# 4_Ethernet_PHY.net
KiCad netlist of a schematic drawn in Altium Designer
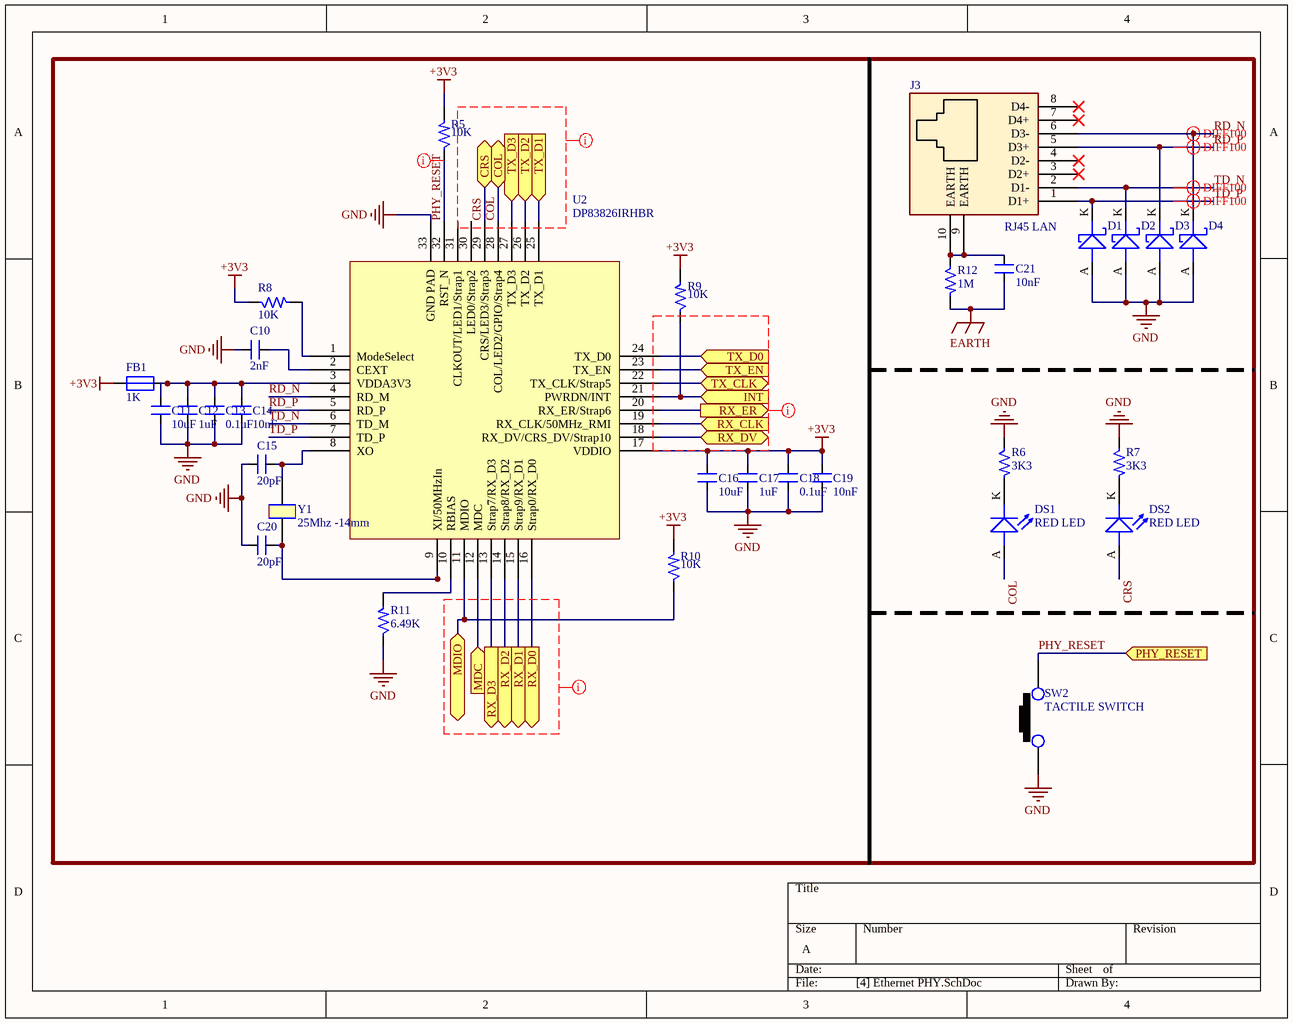
[diagram p0: [4] Ethernet PHY.SchDoc]

(export (version "E")
  (design (tool "Eeschema 10.0.6"))
  (components
    (comp (ref "C10")
      (value "2nF")
      (footprint "CAP_0805")
      (description "2000pF ±10% 50V Ceramic Capacitor X7R 0805 (2012 Metric)")
      (fields
        (field (name "MANUFACTURER") "Samsung Electro-Mechanics")
        (field (name "MANUFACTURER PART NUMBER") "CL21B202KBANNNC")
      )
      (libsource (lib "ESTEEMPCBLIB") (part "CAP_2nF-50V-10%-0805"))
    )
    (comp (ref "C11")
      (value "10uF")
      (footprint "CAP_1206")
      (description "10µF ±10% 50V Ceramic Capacitor X7R 1206 (3216 Metric)")
      (fields
        (field (name "MANUFACTURER") "KEMET")
        (field (name "MANUFACTURER PART NUMBER") "CL31B106KBHNNNE")
      )
      (libsource (lib "ESTEEMPCBLIB") (part "CAP_10uF-50V-10%-1206"))
    )
    (comp (ref "C12")
      (value "1uF")
      (footprint "CAP_0805")
      (description "1µF ±5% 50V Ceramic Capacitor X7R 0805 (2012 Metric)")
      (fields
        (field (name "MANUFACTURER") "Samsung")
        (field (name "MANUFACTURER PART NUMBER") "CC0805JKX7R9BB105")
      )
      (libsource (lib "ESTEEMPCBLIB") (part "CAP_1uF-50V-5%-0805"))
    )
    (comp (ref "C13")
      (value "0.1uF")
      (footprint "CAP_0805")
      (description "0.1µF ±10% 50V Ceramic Capacitor X7R 0805 (2012 Metric)")
      (fields
        (field (name "MANUFACTURER") "Samsung")
        (field (name "MANUFACTURER PART NUMBER") "CL21B104KBCNNNC")
      )
      (libsource (lib "ESTEEMPCBLIB") (part "CAP_0.1uF-50V-10%-0805"))
    )
    (comp (ref "C14")
      (value "10nF")
      (footprint "CAP_0805")
      (description "10000pF ±10% 50V Ceramic Capacitor X7R 0805 (2012 Metric)")
      (fields
        (field (name "MANUFACTURER") "Samsung")
        (field (name "MANUFACTURER PART NUMBER") "C0805C103K5RECAUTO")
      )
      (libsource (lib "ESTEEMPCBLIB") (part "CAP_10nF-50V-10%-0805"))
    )
    (comp (ref "C15")
      (value "20pF")
      (footprint "CAP_0805")
      (description "±10% 50V Ceramic Capacitor C0G, NP0 0805 (2012 Metric)")
      (fields
        (field (name "MANUFACTURER") "AVX Corporation")
        (field (name "MANUFACTURER PART NUMBER") "08055A200KAT2A")
      )
      (libsource (lib "ESTEEMPCBLIB") (part "CAP_20pF-50V-10%-0805"))
    )
    (comp (ref "C16")
      (value "10uF")
      (footprint "CAP_1206")
      (description "10µF ±10% 50V Ceramic Capacitor X7R 1206 (3216 Metric)")
      (fields
        (field (name "MANUFACTURER") "KEMET")
        (field (name "MANUFACTURER PART NUMBER") "CL31B106KBHNNNE")
      )
      (libsource (lib "ESTEEMPCBLIB") (part "CAP_10uF-50V-10%-1206"))
    )
    (comp (ref "C17")
      (value "1uF")
      (footprint "CAP_0805")
      (description "1µF ±5% 50V Ceramic Capacitor X7R 0805 (2012 Metric)")
      (fields
        (field (name "MANUFACTURER") "Samsung")
        (field (name "MANUFACTURER PART NUMBER") "CC0805JKX7R9BB105")
      )
      (libsource (lib "ESTEEMPCBLIB") (part "CAP_1uF-50V-5%-0805"))
    )
    (comp (ref "C18")
      (value "0.1uF")
      (footprint "CAP_0805")
      (description "0.1µF ±10% 50V Ceramic Capacitor X7R 0805 (2012 Metric)")
      (fields
        (field (name "MANUFACTURER") "Samsung")
        (field (name "MANUFACTURER PART NUMBER") "CL21B104KBCNNNC")
      )
      (libsource (lib "ESTEEMPCBLIB") (part "CAP_0.1uF-50V-10%-0805"))
    )
    (comp (ref "C19")
      (value "10nF")
      (footprint "CAP_0805")
      (description "10000pF ±10% 50V Ceramic Capacitor X7R 0805 (2012 Metric)")
      (fields
        (field (name "MANUFACTURER") "Samsung")
        (field (name "MANUFACTURER PART NUMBER") "C0805C103K5RECAUTO")
      )
      (libsource (lib "ESTEEMPCBLIB") (part "CAP_10nF-50V-10%-0805"))
    )
    (comp (ref "C20")
      (value "20pF")
      (footprint "CAP_0805")
      (description "±10% 50V Ceramic Capacitor C0G, NP0 0805 (2012 Metric)")
      (fields
        (field (name "MANUFACTURER") "AVX Corporation")
        (field (name "MANUFACTURER PART NUMBER") "08055A200KAT2A")
      )
      (libsource (lib "ESTEEMPCBLIB") (part "CAP_20pF-50V-10%-0805"))
    )
    (comp (ref "C21")
      (value "10nF")
      (footprint "CAP_P196_102X287_H332_RAD_TH")
      (description "10000pF ±10% 1000V (1kV) Ceramic Capacitor X7R Radial")
      (fields
        (field (name "MANUFACTURER") "Yageo")
        (field (name "MANUFACTURER PART NUMBER") "RDER73A103K2K1H03B")
      )
      (libsource (lib "ESTEEMPCBLIB") (part "CAP_10nF-1KV-10%-RAD-TH"))
    )
    (comp (ref "D1")
      (value "ESD3V3D9-TP")
      (footprint "DIO_SOD-923")
      (description "8.8V Clamp 5A (8/20µs) Ipp Tvs Diode Surface Mount SOD-923")
      (fields (field (name "MANUFACTURER") "Micro Commercial Co"))
      (libsource (lib "ESTEEMPCBLIB") (part "DIO-T_3.3V-8.8V-SOD923"))
    )
    (comp (ref "D2")
      (value "ESD3V3D9-TP")
      (footprint "DIO_SOD-923")
      (description "8.8V Clamp 5A (8/20µs) Ipp Tvs Diode Surface Mount SOD-923")
      (fields (field (name "MANUFACTURER") "Micro Commercial Co"))
      (libsource (lib "ESTEEMPCBLIB") (part "DIO-T_3.3V-8.8V-SOD923"))
    )
    (comp (ref "D3")
      (value "ESD3V3D9-TP")
      (footprint "DIO_SOD-923")
      (description "8.8V Clamp 5A (8/20µs) Ipp Tvs Diode Surface Mount SOD-923")
      (fields (field (name "MANUFACTURER") "Micro Commercial Co"))
      (libsource (lib "ESTEEMPCBLIB") (part "DIO-T_3.3V-8.8V-SOD923"))
    )
    (comp (ref "D4")
      (value "ESD3V3D9-TP")
      (footprint "DIO_SOD-923")
      (description "8.8V Clamp 5A (8/20µs) Ipp Tvs Diode Surface Mount SOD-923")
      (fields (field (name "MANUFACTURER") "Micro Commercial Co"))
      (libsource (lib "ESTEEMPCBLIB") (part "DIO-T_3.3V-8.8V-SOD923"))
    )
    (comp (ref "DS1")
      (value "RED LED")
      (footprint "LED_0805")
      (description "Red 631nm LED Indication - Discrete 2V 0805 (2012 Metric)")
      (fields
        (field (name "MANUFACTURER") "Vishay Lite-On")
        (field (name "MANUFACTURER PART NUMBER") "LTST-C171KRKT")
      )
      (libsource (lib "ESTEEMPCBLIB") (part "LED_RED-2V-20mA-0805"))
    )
    (comp (ref "DS2")
      (value "RED LED")
      (footprint "LED_0805")
      (description "Red 631nm LED Indication - Discrete 2V 0805 (2012 Metric)")
      (fields
        (field (name "MANUFACTURER") "Vishay Lite-On")
        (field (name "MANUFACTURER PART NUMBER") "LTST-C171KRKT")
      )
      (libsource (lib "ESTEEMPCBLIB") (part "LED_RED-2V-20mA-0805"))
    )
    (comp (ref "FB1")
      (value "1K")
      (footprint "IND_0805")
      (description "1 kOhms @ 100MHz 1 Power Line Ferrite Bead 0805 (2012 Metric) 1.6A")
      (fields
        (field (name "MANUFACTURER") "Laird")
        (field (name "MANUFACTURER PART NUMBER") "BLM21SP102SH1D")
      )
      (libsource (lib "ESTEEMPCBLIB") (part "FB_1K-100MHZ-1.6A-0805"))
    )
    (comp (ref "J3")
      (value "RJ45 LAN")
      (footprint "CON10_P106_RJ45_TH_ST")
      (description "8 Pins, 2 Row 2.54mm Pitch, right angle Connector, male")
      (fields
        (field (name "MANUFACTURER") "Assmann")
        (field (name "MANUFACTURER PART NUMBER") "A-2004-2-4-LPS-N-R")
      )
      (libsource (lib "ESTEEMPCBLIB") (part "CON-SKT-RJ_8C8P-RA-TH"))
    )
    (comp (ref "R5")
      (value "10K")
      (footprint "RES_0603")
      (description "10 kOhms ±1% 0.1W, 1/10W Chip Resistor 0603 (1608 Metric) Automotive AEC-Q200 Thick Film")
      (fields (field (name "MANUFACTURER") "Walsin") (field (name "MANUFACTURER PART NUMBER") "WR06X1002FTL"))
      (libsource (lib "ESTEEMPCBLIB") (part "RES_10K-0.1W-1%-0603"))
    )
    (comp (ref "R6")
      (value "3K3")
      (footprint "RES_0603")
      (description "3.3 kOhms ±1% 0.1W, 1/10W Chip Resistor 0603 (1608 Metric) Automotive AEC-Q200 Thick Film")
      (fields (field (name "MANUFACTURER") "Wilson") (field (name "MANUFACTURER PART NUMBER") "WR06X3301FTL"))
      (libsource (lib "ESTEEMPCBLIB") (part "RES_3.3K-0.1W-1%-0603"))
    )
    (comp (ref "R7")
      (value "3K3")
      (footprint "RES_0603")
      (description "3.3 kOhms ±1% 0.1W, 1/10W Chip Resistor 0603 (1608 Metric) Automotive AEC-Q200 Thick Film")
      (fields (field (name "MANUFACTURER") "Wilson") (field (name "MANUFACTURER PART NUMBER") "WR06X3301FTL"))
      (libsource (lib "ESTEEMPCBLIB") (part "RES_3.3K-0.1W-1%-0603"))
    )
    (comp (ref "R8")
      (value "10K")
      (footprint "RES_0603")
      (description "10 kOhms ±1% 0.1W, 1/10W Chip Resistor 0603 (1608 Metric) Automotive AEC-Q200 Thick Film")
      (fields (field (name "MANUFACTURER") "Walsin") (field (name "MANUFACTURER PART NUMBER") "WR06X1002FTL"))
      (libsource (lib "ESTEEMPCBLIB") (part "RES_10K-0.1W-1%-0603"))
    )
    (comp (ref "R9")
      (value "10K")
      (footprint "RES_0603")
      (description "10 kOhms ±1% 0.1W, 1/10W Chip Resistor 0603 (1608 Metric) Automotive AEC-Q200 Thick Film")
      (fields (field (name "MANUFACTURER") "Walsin") (field (name "MANUFACTURER PART NUMBER") "WR06X1002FTL"))
      (libsource (lib "ESTEEMPCBLIB") (part "RES_10K-0.1W-1%-0603"))
    )
    (comp (ref "R10")
      (value "10K")
      (footprint "RES_0603")
      (description "10 kOhms ±1% 0.1W, 1/10W Chip Resistor 0603 (1608 Metric) Automotive AEC-Q200 Thick Film")
      (fields (field (name "MANUFACTURER") "Walsin") (field (name "MANUFACTURER PART NUMBER") "WR06X1002FTL"))
      (libsource (lib "ESTEEMPCBLIB") (part "RES_10K-0.1W-1%-0603"))
    )
    (comp (ref "R11")
      (value "6.49K")
      (footprint "RES_0805")
      (description "6.49 kOhms ±1% 0.125W, 1/8W Chip Resistor 0805 (2012 Metric) Moisture Resistant Thick Film")
      (fields
        (field (name "MANUFACTURER") "Stackpole Electronics")
        (field (name "MANUFACTURER PART NUMBER") "RC0805FR-076K49L")
      )
      (libsource (lib "ESTEEMPCBLIB") (part "RES_6.49K-0.125W-1%-0805"))
    )
    (comp (ref "R12")
      (value "1M")
      (footprint "RES_1206")
      (fields (field (name "MANUFACTURER") "Walsin") (field (name "MANUFACTURER PART NUMBER") "WR12X1004FTL"))
      (libsource (lib "ESTEEMPCBLIB") (part "RES_1M-0.25W-1%-1206"))
    )
    (comp (ref "SW2")
      (value "TACTILE SWITCH")
      (footprint "SW_342_SMD")
      (description "Tactile Switch SPST-NO Top Actuated Surface Mount")
      (fields
        (field (name "MANUFACTURER") "ITT C&K")
        (field (name "MANUFACTURER PART NUMBER") "RS-282G05A3-SMRT")
      )
      (libsource (lib "ESTEEMPCBLIB") (part "SW1_RS-282G05A3-SMRT-SMD"))
    )
    (comp (ref "U2")
      (value "DP83826IRHBR")
      (footprint "VQFN32_19_218_23X9_SMD")
      (fields (field (name "MANUFACTURER") "Texas Instruments"))
      (libsource (lib "ESTEEMPCBLIB") (part "IC_DP83826IRHBR"))
    )
    (comp (ref "Y1")
      (value "25Mhz -14mm")
      (footprint "XTAL_314_240X47_SMD")
      (description "25MHz ±30ppm Crystal 20pF 30 Ohms HC-49/US")
      (fields
        (field (name "MANUFACTURER") "Abracon")
        (field (name "MANUFACTURER PART NUMBER") "FOXSDLF/250F-20")
      )
      (libsource (lib "ESTEEMPCBLIB") (part "XTAL_25Mhz-FOXSDLF/250F-20"))
    )
  )
  (nets
    (net (code "1") (name "+3V3") (class "Default")
      (node (ref "C16") (pin "2") (pinfunction "2_2") (pintype "passive"))
      (node (ref "C17") (pin "2") (pinfunction "2_2") (pintype "passive"))
      (node (ref "C18") (pin "2") (pinfunction "2_2") (pintype "passive"))
      (node (ref "C19") (pin "2") (pinfunction "2_2") (pintype "passive"))
      (node (ref "FB1") (pin "1") (pinfunction "1_1") (pintype "passive"))
      (node (ref "R10") (pin "2") (pinfunction "2_2") (pintype "passive"))
      (node (ref "R5") (pin "2") (pinfunction "2_2") (pintype "passive"))
      (node (ref "R8") (pin "1") (pinfunction "1_1") (pintype "passive"))
      (node (ref "R9") (pin "2") (pinfunction "2_2") (pintype "passive"))
      (node (ref "U2") (pin "17") (pinfunction "VDDIO_17") (pintype "passive"))
    )
    (net (code "2") (name "/COL") (class "Default")
      (node (ref "DS1") (pin "A") (pinfunction "ANODE_A") (pintype "passive"))
      (node (ref "U2") (pin "28") (pinfunction "COL/LED2/GPIO/Strap4_28") (pintype "passive"))
    )
    (net (code "3") (name "/CRS") (class "Default")
      (node (ref "DS2") (pin "A") (pinfunction "ANODE_A") (pintype "passive"))
      (node (ref "U2") (pin "29") (pinfunction "CRS/LED3/Strap3_29") (pintype "passive"))
    )
    (net (code "4") (name "/INT") (class "Default")
      (node (ref "R9") (pin "1") (pinfunction "1_1") (pintype "passive"))
      (node (ref "U2") (pin "21") (pinfunction "PWRDN/INT_21") (pintype "passive"))
    )
    (net (code "5") (name "/MDC") (class "Default")
      (node (ref "U2") (pin "12") (pinfunction "MDC_12") (pintype "passive"))
    )
    (net (code "6") (name "/MDIO") (class "Default")
      (node (ref "R10") (pin "1") (pinfunction "1_1") (pintype "passive"))
      (node (ref "U2") (pin "11") (pinfunction "MDIO_11") (pintype "passive"))
    )
    (net (code "7") (name "/PHY_RESET") (class "Default")
      (node (ref "R5") (pin "1") (pinfunction "1_1") (pintype "passive"))
      (node (ref "SW2") (pin "2") (pinfunction "2_2") (pintype "passive"))
      (node (ref "U2") (pin "32") (pinfunction "RST_N_32") (pintype "passive"))
    )
    (net (code "8") (name "/RD_N") (class "Default")
      (node (ref "D4") (pin "K") (pinfunction "K_K") (pintype "passive"))
      (node (ref "J3") (pin "6") (pinfunction "D3-_6") (pintype "passive"))
      (node (ref "U2") (pin "4") (pinfunction "RD_M_4") (pintype "passive"))
    )
    (net (code "9") (name "/RD_P") (class "Default")
      (node (ref "D3") (pin "K") (pinfunction "K_K") (pintype "passive"))
      (node (ref "J3") (pin "5") (pinfunction "D3+_5") (pintype "passive"))
      (node (ref "U2") (pin "5") (pinfunction "RD_P_5") (pintype "passive"))
    )
    (net (code "10") (name "/RX_CLK") (class "Default")
      (node (ref "U2") (pin "19") (pinfunction "RX_CLK/50MHz_RMI_19") (pintype "passive"))
    )
    (net (code "11") (name "/RX_D0") (class "Default")
      (node (ref "U2") (pin "16") (pinfunction "Strap0/RX_D0_16") (pintype "passive"))
    )
    (net (code "12") (name "/RX_D1") (class "Default")
      (node (ref "U2") (pin "15") (pinfunction "Strap9/RX_D1_15") (pintype "passive"))
    )
    (net (code "13") (name "/RX_D2") (class "Default")
      (node (ref "U2") (pin "14") (pinfunction "Strap8/RX_D2_14") (pintype "passive"))
    )
    (net (code "14") (name "/RX_D3") (class "Default")
      (node (ref "U2") (pin "13") (pinfunction "Strap7/RX_D3_13") (pintype "passive"))
    )
    (net (code "15") (name "/RX_DV") (class "Default")
      (node (ref "U2") (pin "18") (pinfunction "RX_DV/CRS_DV/Strap10_18") (pintype "passive"))
    )
    (net (code "16") (name "/RX_ER") (class "Default")
      (node (ref "U2") (pin "20") (pinfunction "RX_ER/Strap6_20") (pintype "passive"))
    )
    (net (code "17") (name "/TD_N") (class "Default")
      (node (ref "D2") (pin "K") (pinfunction "K_K") (pintype "passive"))
      (node (ref "J3") (pin "2") (pinfunction "D1-_2") (pintype "passive"))
      (node (ref "U2") (pin "6") (pinfunction "TD_M_6") (pintype "passive"))
    )
    (net (code "18") (name "/TD_P") (class "Default")
      (node (ref "D1") (pin "K") (pinfunction "K_K") (pintype "passive"))
      (node (ref "J3") (pin "1") (pinfunction "D1+_1") (pintype "passive"))
      (node (ref "U2") (pin "7") (pinfunction "TD_P_7") (pintype "passive"))
    )
    (net (code "19") (name "/TX_CLK") (class "Default")
      (node (ref "U2") (pin "22") (pinfunction "TX_CLK/Strap5_22") (pintype "passive"))
    )
    (net (code "20") (name "/TX_D0") (class "Default")
      (node (ref "U2") (pin "24") (pinfunction "TX_D0_24") (pintype "passive"))
    )
    (net (code "21") (name "/TX_D1") (class "Default")
      (node (ref "U2") (pin "25") (pinfunction "TX_D1_25") (pintype "passive"))
    )
    (net (code "22") (name "/TX_D2") (class "Default")
      (node (ref "U2") (pin "26") (pinfunction "TX_D2_26") (pintype "passive"))
    )
    (net (code "23") (name "/TX_D3") (class "Default")
      (node (ref "U2") (pin "27") (pinfunction "TX_D3_27") (pintype "passive"))
    )
    (net (code "24") (name "/TX_EN") (class "Default")
      (node (ref "U2") (pin "23") (pinfunction "TX_EN_23") (pintype "passive"))
    )
    (net (code "25") (name "EARTH") (class "Default")
      (node (ref "C21") (pin "1") (pinfunction "1_1") (pintype "passive"))
      (node (ref "R12") (pin "2") (pinfunction "2_2") (pintype "passive"))
    )
    (net (code "26") (name "GND") (class "Default")
      (node (ref "C10") (pin "1") (pinfunction "1_1") (pintype "passive"))
      (node (ref "C11") (pin "1") (pinfunction "1_1") (pintype "passive"))
      (node (ref "C12") (pin "1") (pinfunction "1_1") (pintype "passive"))
      (node (ref "C13") (pin "1") (pinfunction "1_1") (pintype "passive"))
      (node (ref "C14") (pin "1") (pinfunction "1_1") (pintype "passive"))
      (node (ref "C15") (pin "1") (pinfunction "1_1") (pintype "passive"))
      (node (ref "C16") (pin "1") (pinfunction "1_1") (pintype "passive"))
      (node (ref "C17") (pin "1") (pinfunction "1_1") (pintype "passive"))
      (node (ref "C18") (pin "1") (pinfunction "1_1") (pintype "passive"))
      (node (ref "C19") (pin "1") (pinfunction "1_1") (pintype "passive"))
      (node (ref "C20") (pin "1") (pinfunction "1_1") (pintype "passive"))
      (node (ref "D1") (pin "A") (pinfunction "A_A") (pintype "passive"))
      (node (ref "D2") (pin "A") (pinfunction "A_A") (pintype "passive"))
      (node (ref "D3") (pin "A") (pinfunction "A_A") (pintype "passive"))
      (node (ref "D4") (pin "A") (pinfunction "A_A") (pintype "passive"))
      (node (ref "R11") (pin "1") (pinfunction "1_1") (pintype "passive"))
      (node (ref "R6") (pin "1") (pinfunction "1_1") (pintype "passive"))
      (node (ref "R7") (pin "1") (pinfunction "1_1") (pintype "passive"))
      (node (ref "SW2") (pin "1") (pinfunction "1_1") (pintype "passive"))
      (node (ref "U2") (pin "33") (pinfunction "GND_PAD_33") (pintype "passive"))
    )
    (net (code "27") (name "Net-(C21-Pad2)") (class "Default")
      (node (ref "C21") (pin "2") (pinfunction "2_2") (pintype "passive"))
      (node (ref "J3") (pin "10") (pinfunction "EARTH_10") (pintype "passive"))
      (node (ref "J3") (pin "9") (pinfunction "EARTH_9") (pintype "passive"))
      (node (ref "R12") (pin "1") (pinfunction "1_1") (pintype "passive"))
    )
    (net (code "28") (name "Net-(DS1-CATHODE)") (class "Default")
      (node (ref "DS1") (pin "K") (pinfunction "CATHODE_K") (pintype "passive"))
      (node (ref "R6") (pin "2") (pinfunction "2_2") (pintype "passive"))
    )
    (net (code "29") (name "Net-(DS2-CATHODE)") (class "Default")
      (node (ref "DS2") (pin "K") (pinfunction "CATHODE_K") (pintype "passive"))
      (node (ref "R7") (pin "2") (pinfunction "2_2") (pintype "passive"))
    )
    (net (code "30") (name "Net-(U2-CEXT)") (class "Default")
      (node (ref "C10") (pin "2") (pinfunction "2_2") (pintype "passive"))
      (node (ref "U2") (pin "2") (pinfunction "CEXT_2") (pintype "passive"))
    )
    (net (code "31") (name "Net-(U2-ModeSelect)") (class "Default")
      (node (ref "R8") (pin "2") (pinfunction "2_2") (pintype "passive"))
      (node (ref "U2") (pin "1") (pinfunction "ModeSelect_1") (pintype "passive"))
    )
    (net (code "32") (name "Net-(U2-RBIAS)") (class "Default")
      (node (ref "R11") (pin "2") (pinfunction "2_2") (pintype "passive"))
      (node (ref "U2") (pin "10") (pinfunction "RBIAS_10") (pintype "passive"))
    )
    (net (code "33") (name "Net-(U2-VDDA3V3)") (class "Default")
      (node (ref "C11") (pin "2") (pinfunction "2_2") (pintype "passive"))
      (node (ref "C12") (pin "2") (pinfunction "2_2") (pintype "passive"))
      (node (ref "C13") (pin "2") (pinfunction "2_2") (pintype "passive"))
      (node (ref "C14") (pin "2") (pinfunction "2_2") (pintype "passive"))
      (node (ref "FB1") (pin "2") (pinfunction "2_2") (pintype "passive"))
      (node (ref "U2") (pin "3") (pinfunction "VDDA3V3_3") (pintype "passive"))
    )
    (net (code "34") (name "Net-(U2-XI{slash}50MHzIn)") (class "Default")
      (node (ref "C20") (pin "2") (pinfunction "2_2") (pintype "passive"))
      (node (ref "U2") (pin "9") (pinfunction "XI/50MHzIn_9") (pintype "passive"))
      (node (ref "Y1") (pin "1") (pinfunction "1_1") (pintype "passive"))
    )
    (net (code "35") (name "Net-(U2-XO)") (class "Default")
      (node (ref "C15") (pin "2") (pinfunction "2_2") (pintype "passive"))
      (node (ref "U2") (pin "8") (pinfunction "XO_8") (pintype "passive"))
      (node (ref "Y1") (pin "2") (pinfunction "2_2") (pintype "passive"))
    )
    (net (code "36") (name "unconnected-(J3-D2+-Pad3)") (class "Default")
      (node (ref "J3") (pin "3") (pinfunction "D2+_3") (pintype "passive+no_connect"))
    )
    (net (code "37") (name "unconnected-(J3-D2--Pad4)") (class "Default")
      (node (ref "J3") (pin "4") (pinfunction "D2-_4") (pintype "passive+no_connect"))
    )
    (net (code "38") (name "unconnected-(J3-D4+-Pad7)") (class "Default")
      (node (ref "J3") (pin "7") (pinfunction "D4+_7") (pintype "passive+no_connect"))
    )
    (net (code "39") (name "unconnected-(J3-D4--Pad8)") (class "Default")
      (node (ref "J3") (pin "8") (pinfunction "D4-_8") (pintype "passive+no_connect"))
    )
    (net (code "40") (name "unconnected-(U2-CLKOUT{slash}LED1{slash}Strap1-Pad31)") (class "Default")
      (node (ref "U2") (pin "31") (pinfunction "CLKOUT/LED1/Strap1_31") (pintype "passive"))
    )
    (net (code "41") (name "unconnected-(U2-LED0{slash}Strap2-Pad30)") (class "Default")
      (node (ref "U2") (pin "30") (pinfunction "LED0/Strap2_30") (pintype "passive"))
    )
  )
)
